# ElectricalDiagram.net
KiCad netlist of a schematic drawn in EAGLE
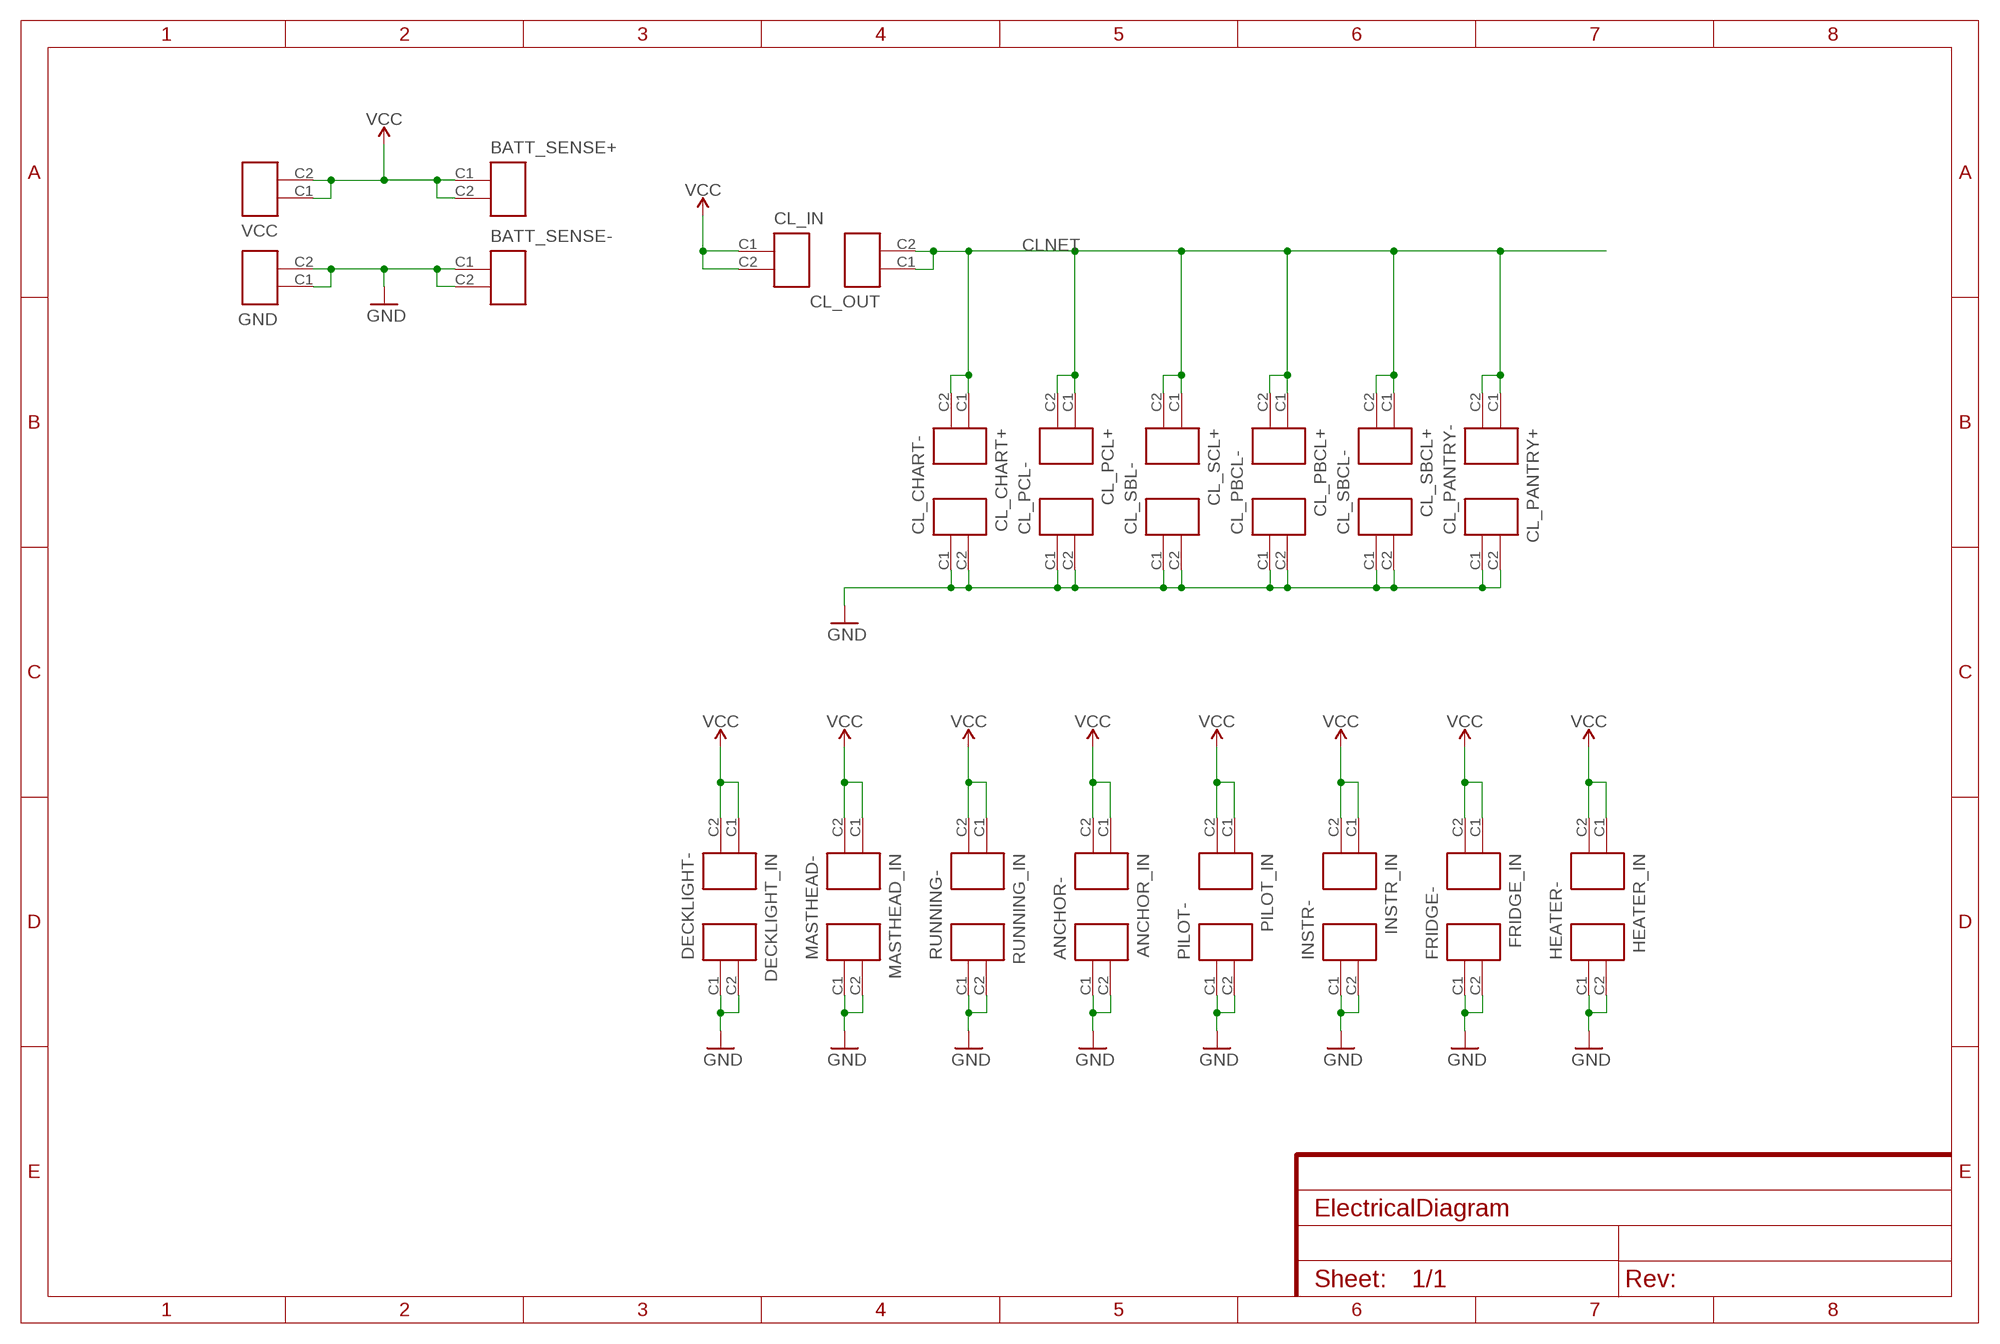
[diagram p0: schematic, sheet 1]

(export (version "E")
  (design (tool "Eeschema 10.0.6"))
  (components
    (comp (ref "ANCHOR-")
      (value "1201-01-001-SPADE")
      (footprint "eagle-import:1201-01-001-SPADE")
      (libsource (lib "eagle-import") (part "1201-01-001-SPADE"))
    )
    (comp (ref "ANCHOR_IN")
      (value "1201-01-001-SPADE")
      (footprint "eagle-import:1201-01-001-SPADE")
      (libsource (lib "eagle-import") (part "1201-01-001-SPADE"))
    )
    (comp (ref "BATT_SENSE+")
      (value "1201-01-001-SPADE")
      (footprint "eagle-import:1201-01-001-SPADE")
      (libsource (lib "eagle-import") (part "1201-01-001-SPADE"))
    )
    (comp (ref "BATT_SENSE-")
      (value "1201-01-001-SPADE")
      (footprint "eagle-import:1201-01-001-SPADE")
      (libsource (lib "eagle-import") (part "1201-01-001-SPADE"))
    )
    (comp (ref "CL_CHART+")
      (value "1201-01-001-SPADE")
      (footprint "eagle-import:1201-01-001-SPADE")
      (libsource (lib "eagle-import") (part "1201-01-001-SPADE"))
    )
    (comp (ref "CL_CHART-")
      (value "1201-01-001-SPADE")
      (footprint "eagle-import:1201-01-001-SPADE")
      (libsource (lib "eagle-import") (part "1201-01-001-SPADE"))
    )
    (comp (ref "CL_IN")
      (value "1201-01-001-SPADE")
      (footprint "eagle-import:1201-01-001-SPADE")
      (libsource (lib "eagle-import") (part "1201-01-001-SPADE"))
    )
    (comp (ref "CL_OUT")
      (value "1201-01-001-SPADE")
      (footprint "eagle-import:1201-01-001-SPADE")
      (libsource (lib "eagle-import") (part "1201-01-001-SPADE"))
    )
    (comp (ref "CL_PANTRY+")
      (value "1201-01-001-SPADE")
      (footprint "eagle-import:1201-01-001-SPADE")
      (libsource (lib "eagle-import") (part "1201-01-001-SPADE"))
    )
    (comp (ref "CL_PANTRY-")
      (value "1201-01-001-SPADE")
      (footprint "eagle-import:1201-01-001-SPADE")
      (libsource (lib "eagle-import") (part "1201-01-001-SPADE"))
    )
    (comp (ref "CL_PBCL+")
      (value "1201-01-001-SPADE")
      (footprint "eagle-import:1201-01-001-SPADE")
      (libsource (lib "eagle-import") (part "1201-01-001-SPADE"))
    )
    (comp (ref "CL_PBCL-")
      (value "1201-01-001-SPADE")
      (footprint "eagle-import:1201-01-001-SPADE")
      (libsource (lib "eagle-import") (part "1201-01-001-SPADE"))
    )
    (comp (ref "CL_PCL+")
      (value "1201-01-001-SPADE")
      (footprint "eagle-import:1201-01-001-SPADE")
      (libsource (lib "eagle-import") (part "1201-01-001-SPADE"))
    )
    (comp (ref "CL_PCL-")
      (value "1201-01-001-SPADE")
      (footprint "eagle-import:1201-01-001-SPADE")
      (libsource (lib "eagle-import") (part "1201-01-001-SPADE"))
    )
    (comp (ref "CL_SBCL+")
      (value "1201-01-001-SPADE")
      (footprint "eagle-import:1201-01-001-SPADE")
      (libsource (lib "eagle-import") (part "1201-01-001-SPADE"))
    )
    (comp (ref "CL_SBCL-")
      (value "1201-01-001-SPADE")
      (footprint "eagle-import:1201-01-001-SPADE")
      (libsource (lib "eagle-import") (part "1201-01-001-SPADE"))
    )
    (comp (ref "CL_SBL-")
      (value "1201-01-001-SPADE")
      (footprint "eagle-import:1201-01-001-SPADE")
      (libsource (lib "eagle-import") (part "1201-01-001-SPADE"))
    )
    (comp (ref "CL_SCL+")
      (value "1201-01-001-SPADE")
      (footprint "eagle-import:1201-01-001-SPADE")
      (libsource (lib "eagle-import") (part "1201-01-001-SPADE"))
    )
    (comp (ref "DECKLIGHT-")
      (value "1201-01-001-SPADE")
      (footprint "eagle-import:1201-01-001-SPADE")
      (libsource (lib "eagle-import") (part "1201-01-001-SPADE"))
    )
    (comp (ref "DECKLIGHT_IN")
      (value "1201-01-001-SPADE")
      (footprint "eagle-import:1201-01-001-SPADE")
      (libsource (lib "eagle-import") (part "1201-01-001-SPADE"))
    )
    (comp (ref "FRIDGE-")
      (value "1201-01-001-SPADE")
      (footprint "eagle-import:1201-01-001-SPADE")
      (libsource (lib "eagle-import") (part "1201-01-001-SPADE"))
    )
    (comp (ref "FRIDGE_IN")
      (value "1201-01-001-SPADE")
      (footprint "eagle-import:1201-01-001-SPADE")
      (libsource (lib "eagle-import") (part "1201-01-001-SPADE"))
    )
    (comp (ref "GND")
      (value "1201-01-001-SPADE")
      (footprint "eagle-import:1201-01-001-SPADE")
      (libsource (lib "eagle-import") (part "1201-01-001-SPADE"))
    )
    (comp (ref "HEATER-")
      (value "1201-01-001-SPADE")
      (footprint "eagle-import:1201-01-001-SPADE")
      (libsource (lib "eagle-import") (part "1201-01-001-SPADE"))
    )
    (comp (ref "HEATER_IN")
      (value "1201-01-001-SPADE")
      (footprint "eagle-import:1201-01-001-SPADE")
      (libsource (lib "eagle-import") (part "1201-01-001-SPADE"))
    )
    (comp (ref "INSTR-")
      (value "1201-01-001-SPADE")
      (footprint "eagle-import:1201-01-001-SPADE")
      (libsource (lib "eagle-import") (part "1201-01-001-SPADE"))
    )
    (comp (ref "INSTR_IN")
      (value "1201-01-001-SPADE")
      (footprint "eagle-import:1201-01-001-SPADE")
      (libsource (lib "eagle-import") (part "1201-01-001-SPADE"))
    )
    (comp (ref "MASTHEAD-")
      (value "1201-01-001-SPADE")
      (footprint "eagle-import:1201-01-001-SPADE")
      (libsource (lib "eagle-import") (part "1201-01-001-SPADE"))
    )
    (comp (ref "MASTHEAD_IN")
      (value "1201-01-001-SPADE")
      (footprint "eagle-import:1201-01-001-SPADE")
      (libsource (lib "eagle-import") (part "1201-01-001-SPADE"))
    )
    (comp (ref "PILOT-")
      (value "1201-01-001-SPADE")
      (footprint "eagle-import:1201-01-001-SPADE")
      (libsource (lib "eagle-import") (part "1201-01-001-SPADE"))
    )
    (comp (ref "PILOT_IN")
      (value "1201-01-001-SPADE")
      (footprint "eagle-import:1201-01-001-SPADE")
      (libsource (lib "eagle-import") (part "1201-01-001-SPADE"))
    )
    (comp (ref "RUNNING-")
      (value "1201-01-001-SPADE")
      (footprint "eagle-import:1201-01-001-SPADE")
      (libsource (lib "eagle-import") (part "1201-01-001-SPADE"))
    )
    (comp (ref "RUNNING_IN")
      (value "1201-01-001-SPADE")
      (footprint "eagle-import:1201-01-001-SPADE")
      (libsource (lib "eagle-import") (part "1201-01-001-SPADE"))
    )
    (comp (ref "VCC")
      (value "1201-01-001-SPADE")
      (footprint "eagle-import:1201-01-001-SPADE")
      (libsource (lib "eagle-import") (part "1201-01-001-SPADE"))
    )
  )
  (nets
    (net (code "1") (name "/CLNET") (class "Default")
      (node (ref "CL_CHART+") (pin "C1") (pinfunction "C1_C1") (pintype "bidirectional"))
      (node (ref "CL_CHART+") (pin "C2") (pinfunction "C2_C2") (pintype "bidirectional"))
      (node (ref "CL_OUT") (pin "C1") (pinfunction "C1_C1") (pintype "bidirectional"))
      (node (ref "CL_OUT") (pin "C2") (pinfunction "C2_C2") (pintype "bidirectional"))
      (node (ref "CL_PANTRY+") (pin "C1") (pinfunction "C1_C1") (pintype "bidirectional"))
      (node (ref "CL_PANTRY+") (pin "C2") (pinfunction "C2_C2") (pintype "bidirectional"))
      (node (ref "CL_PBCL+") (pin "C1") (pinfunction "C1_C1") (pintype "bidirectional"))
      (node (ref "CL_PBCL+") (pin "C2") (pinfunction "C2_C2") (pintype "bidirectional"))
      (node (ref "CL_PCL+") (pin "C1") (pinfunction "C1_C1") (pintype "bidirectional"))
      (node (ref "CL_PCL+") (pin "C2") (pinfunction "C2_C2") (pintype "bidirectional"))
      (node (ref "CL_SBCL+") (pin "C1") (pinfunction "C1_C1") (pintype "bidirectional"))
      (node (ref "CL_SBCL+") (pin "C2") (pinfunction "C2_C2") (pintype "bidirectional"))
      (node (ref "CL_SCL+") (pin "C1") (pinfunction "C1_C1") (pintype "bidirectional"))
      (node (ref "CL_SCL+") (pin "C2") (pinfunction "C2_C2") (pintype "bidirectional"))
    )
    (net (code "2") (name "GND") (class "Default")
      (node (ref "ANCHOR-") (pin "C1") (pinfunction "C1_C1") (pintype "bidirectional"))
      (node (ref "ANCHOR-") (pin "C2") (pinfunction "C2_C2") (pintype "bidirectional"))
      (node (ref "BATT_SENSE-") (pin "C1") (pinfunction "C1_C1") (pintype "bidirectional"))
      (node (ref "BATT_SENSE-") (pin "C2") (pinfunction "C2_C2") (pintype "bidirectional"))
      (node (ref "CL_CHART-") (pin "C1") (pinfunction "C1_C1") (pintype "bidirectional"))
      (node (ref "CL_CHART-") (pin "C2") (pinfunction "C2_C2") (pintype "bidirectional"))
      (node (ref "CL_PANTRY-") (pin "C1") (pinfunction "C1_C1") (pintype "bidirectional"))
      (node (ref "CL_PANTRY-") (pin "C2") (pinfunction "C2_C2") (pintype "bidirectional"))
      (node (ref "CL_PBCL-") (pin "C1") (pinfunction "C1_C1") (pintype "bidirectional"))
      (node (ref "CL_PBCL-") (pin "C2") (pinfunction "C2_C2") (pintype "bidirectional"))
      (node (ref "CL_PCL-") (pin "C1") (pinfunction "C1_C1") (pintype "bidirectional"))
      (node (ref "CL_PCL-") (pin "C2") (pinfunction "C2_C2") (pintype "bidirectional"))
      (node (ref "CL_SBCL-") (pin "C1") (pinfunction "C1_C1") (pintype "bidirectional"))
      (node (ref "CL_SBCL-") (pin "C2") (pinfunction "C2_C2") (pintype "bidirectional"))
      (node (ref "CL_SBL-") (pin "C1") (pinfunction "C1_C1") (pintype "bidirectional"))
      (node (ref "CL_SBL-") (pin "C2") (pinfunction "C2_C2") (pintype "bidirectional"))
      (node (ref "DECKLIGHT-") (pin "C1") (pinfunction "C1_C1") (pintype "bidirectional"))
      (node (ref "DECKLIGHT-") (pin "C2") (pinfunction "C2_C2") (pintype "bidirectional"))
      (node (ref "FRIDGE-") (pin "C1") (pinfunction "C1_C1") (pintype "bidirectional"))
      (node (ref "FRIDGE-") (pin "C2") (pinfunction "C2_C2") (pintype "bidirectional"))
      (node (ref "GND") (pin "C1") (pinfunction "C1_C1") (pintype "bidirectional"))
      (node (ref "GND") (pin "C2") (pinfunction "C2_C2") (pintype "bidirectional"))
      (node (ref "HEATER-") (pin "C1") (pinfunction "C1_C1") (pintype "bidirectional"))
      (node (ref "HEATER-") (pin "C2") (pinfunction "C2_C2") (pintype "bidirectional"))
      (node (ref "INSTR-") (pin "C1") (pinfunction "C1_C1") (pintype "bidirectional"))
      (node (ref "INSTR-") (pin "C2") (pinfunction "C2_C2") (pintype "bidirectional"))
      (node (ref "MASTHEAD-") (pin "C1") (pinfunction "C1_C1") (pintype "bidirectional"))
      (node (ref "MASTHEAD-") (pin "C2") (pinfunction "C2_C2") (pintype "bidirectional"))
      (node (ref "PILOT-") (pin "C1") (pinfunction "C1_C1") (pintype "bidirectional"))
      (node (ref "PILOT-") (pin "C2") (pinfunction "C2_C2") (pintype "bidirectional"))
      (node (ref "RUNNING-") (pin "C1") (pinfunction "C1_C1") (pintype "bidirectional"))
      (node (ref "RUNNING-") (pin "C2") (pinfunction "C2_C2") (pintype "bidirectional"))
    )
    (net (code "3") (name "VCC") (class "Default")
      (node (ref "ANCHOR_IN") (pin "C1") (pinfunction "C1_C1") (pintype "bidirectional"))
      (node (ref "ANCHOR_IN") (pin "C2") (pinfunction "C2_C2") (pintype "bidirectional"))
      (node (ref "BATT_SENSE+") (pin "C1") (pinfunction "C1_C1") (pintype "bidirectional"))
      (node (ref "BATT_SENSE+") (pin "C2") (pinfunction "C2_C2") (pintype "bidirectional"))
      (node (ref "CL_IN") (pin "C1") (pinfunction "C1_C1") (pintype "bidirectional"))
      (node (ref "CL_IN") (pin "C2") (pinfunction "C2_C2") (pintype "bidirectional"))
      (node (ref "DECKLIGHT_IN") (pin "C1") (pinfunction "C1_C1") (pintype "bidirectional"))
      (node (ref "DECKLIGHT_IN") (pin "C2") (pinfunction "C2_C2") (pintype "bidirectional"))
      (node (ref "FRIDGE_IN") (pin "C1") (pinfunction "C1_C1") (pintype "bidirectional"))
      (node (ref "FRIDGE_IN") (pin "C2") (pinfunction "C2_C2") (pintype "bidirectional"))
      (node (ref "HEATER_IN") (pin "C1") (pinfunction "C1_C1") (pintype "bidirectional"))
      (node (ref "HEATER_IN") (pin "C2") (pinfunction "C2_C2") (pintype "bidirectional"))
      (node (ref "INSTR_IN") (pin "C1") (pinfunction "C1_C1") (pintype "bidirectional"))
      (node (ref "INSTR_IN") (pin "C2") (pinfunction "C2_C2") (pintype "bidirectional"))
      (node (ref "MASTHEAD_IN") (pin "C1") (pinfunction "C1_C1") (pintype "bidirectional"))
      (node (ref "MASTHEAD_IN") (pin "C2") (pinfunction "C2_C2") (pintype "bidirectional"))
      (node (ref "PILOT_IN") (pin "C1") (pinfunction "C1_C1") (pintype "bidirectional"))
      (node (ref "PILOT_IN") (pin "C2") (pinfunction "C2_C2") (pintype "bidirectional"))
      (node (ref "RUNNING_IN") (pin "C1") (pinfunction "C1_C1") (pintype "bidirectional"))
      (node (ref "RUNNING_IN") (pin "C2") (pinfunction "C2_C2") (pintype "bidirectional"))
      (node (ref "VCC") (pin "C1") (pinfunction "C1_C1") (pintype "bidirectional"))
      (node (ref "VCC") (pin "C2") (pinfunction "C2_C2") (pintype "bidirectional"))
    )
  )
)
